# -NEW-AQB-5-ANTON_TRANS-PWR-POLYGON.net
KiCad netlist of a schematic drawn in Altium Designer
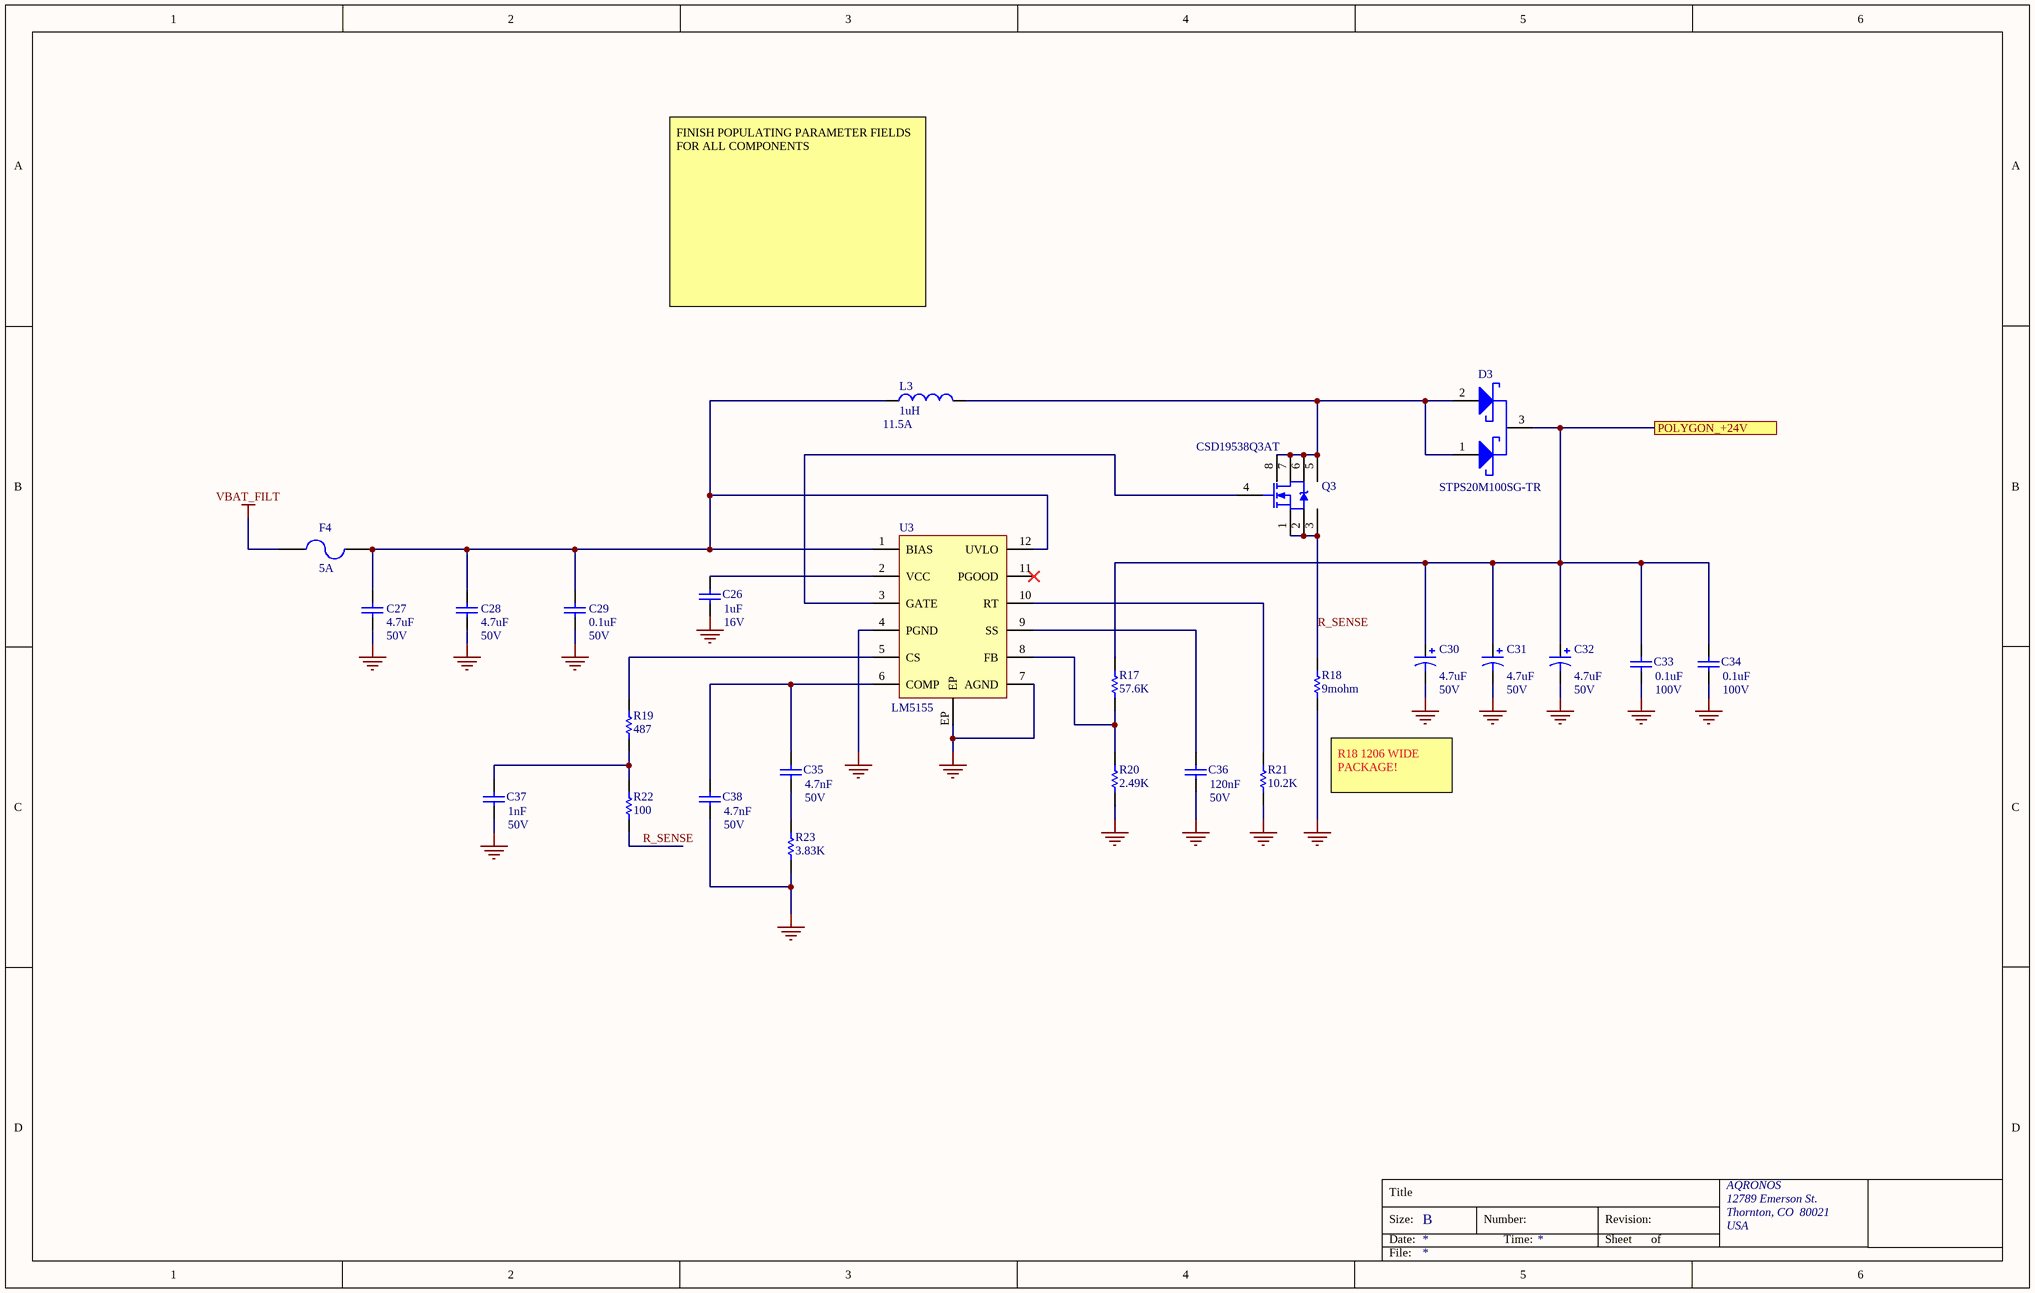
[diagram p0: -NEW-AQB-5-ANTON_TRANS-PWR-POLYGON.SchDoc]

(export (version "E")
  (design (tool "Eeschema 10.0.6"))
  (components
    (comp (ref "C26")
      (value "1uF")
      (footprint "CAP0603")
      (description "CAP CER 1UF 16V X7R 0603")
      (fields
        (field (name "DISTRIBUTOR PART NUMBER") "587-1241-1-ND")
        (field (name "MANUFACTURER PART NUMBER") "EMK107B7105KA-T")
        (field (name "VOLTAGE") "16V")
      )
      (libsource (lib "AQRONOS_TEMP_SCH") (part "Capacitor_non_pol"))
    )
    (comp (ref "C27")
      (value "4.7uF")
      (footprint "CAP0805")
      (description "CAP CER 4.7UF 50V X5R 0805")
      (fields
        (field (name "DISTRIBUTOR PART NUMBER") "445-5980-1-ND")
        (field (name "MANUFACTURER PART NUMBER") "C2012X5R1H475K125AB")
        (field (name "VOLTAGE") "50V")
      )
      (libsource (lib "AQRONOS_TEMP_SCH") (part "Capacitor_non_pol"))
    )
    (comp (ref "C28")
      (value "4.7uF")
      (footprint "CAP0805")
      (description "CAP CER 4.7UF 50V X5R 0805")
      (fields
        (field (name "DISTRIBUTOR PART NUMBER") "445-5980-1-ND")
        (field (name "MANUFACTURER PART NUMBER") "C2012X5R1H475K125AB")
        (field (name "VOLTAGE") "50V")
      )
      (libsource (lib "AQRONOS_TEMP_SCH") (part "Capacitor_non_pol"))
    )
    (comp (ref "C29")
      (value "0.1uF")
      (footprint "CAP0402")
      (description "CAP CER 0.1UF 50V X5R 0402")
      (fields
        (field (name "DISTRIBUTOR PART NUMBER") "445-5942-1-ND")
        (field (name "MANUFACTURER PART NUMBER") "C1005X5R1H104K050BB")
        (field (name "VOLTAGE") "50V")
      )
      (libsource (lib "AQRONOS_TEMP_SCH") (part "Capacitor_non_pol"))
    )
    (comp (ref "C30")
      (value "4.7uF")
      (footprint "CAP1206")
      (description "CAP CER 4.7UF 50V X7R 1206")
      (fields
        (field (name "DISTRIBUTOR PART NUMBER") "490-6521-1-ND")
        (field (name "MANUFACTURER PART NUMBER") "C2012X5R1H475K125AB")
        (field (name "VOLTAGE") "50V")
      )
      (libsource (lib "AQRONOS_TEMP_SCH") (part "Capacitor-Polarized"))
    )
    (comp (ref "C31")
      (value "4.7uF")
      (footprint "CAP1206")
      (description "CAP CER 4.7UF 50V X7R 1206")
      (fields
        (field (name "DISTRIBUTOR PART NUMBER") "490-6521-1-ND")
        (field (name "MANUFACTURER PART NUMBER") "C2012X5R1H475K125AB")
        (field (name "VOLTAGE") "50V")
      )
      (libsource (lib "AQRONOS_TEMP_SCH") (part "Capacitor-Polarized"))
    )
    (comp (ref "C32")
      (value "4.7uF")
      (footprint "CAP1206")
      (description "CAP CER 4.7UF 50V X7R 1206")
      (fields
        (field (name "DISTRIBUTOR PART NUMBER") "490-6521-1-ND")
        (field (name "MANUFACTURER PART NUMBER") "C2012X5R1H475K125AB")
        (field (name "VOLTAGE") "50V")
      )
      (libsource (lib "AQRONOS_TEMP_SCH") (part "Capacitor-Polarized"))
    )
    (comp (ref "C33")
      (value "0.1uF")
      (footprint "CAP0603")
      (description "CAP CER 0.1UF 100V X7R 0603")
      (fields
        (field (name "DISTRIBUTOR PART NUMBER") "490-3285-1-ND")
        (field (name "MANUFACTURER PART NUMBER") "GRM188R72A104KA35D")
        (field (name "VOLTAGE") "100V")
      )
      (libsource (lib "AQRONOS_TEMP_SCH") (part "Capacitor_non_pol"))
    )
    (comp (ref "C34")
      (value "0.1uF")
      (footprint "CAP0603")
      (description "CAP CER 0.1UF 100V X7R 0603")
      (fields
        (field (name "DISTRIBUTOR PART NUMBER") "490-3285-1-ND")
        (field (name "MANUFACTURER PART NUMBER") "GRM188R72A104KA35D")
        (field (name "VOLTAGE") "100V")
      )
      (libsource (lib "AQRONOS_TEMP_SCH") (part "Capacitor_non_pol"))
    )
    (comp (ref "C35")
      (value "4.7nF")
      (footprint "CAP0603")
      (description "CAP CER 4700PF 50V C0G 0603")
      (fields
        (field (name "DISTRIBUTOR PART NUMBER") "445-6912-1-ND")
        (field (name "MANUFACTURER PART NUMBER") "CGA3E2C0G1H472J080AA")
        (field (name "VOLTAGE") "50V")
      )
      (libsource (lib "AQRONOS_TEMP_SCH") (part "Capacitor_non_pol"))
    )
    (comp (ref "C36")
      (value "120nF")
      (footprint "CAP0402")
      (fields
        (field (name "DISTRIBUTOR PART NUMBER") "490-1311-1-ND")
        (field (name "MANUFACTURER PART NUMBER") "C1812C124J5GACTU")
        (field (name "VOLTAGE") "50V")
        (field (name "Comment") "Capacitor_non_pol")
      )
      (libsource (lib "AQRONOS_TEMP_SCH") (part "Capacitor_non_pol"))
    )
    (comp (ref "C37")
      (value "1nF")
      (footprint "CAP0402")
      (description "CAP CER 1000PF 50V C0G/NP0 0402")
      (fields
        (field (name "DISTRIBUTOR PART NUMBER") "490-6190-1-ND")
        (field (name "MANUFACTURER PART NUMBER") "GRM1555C1H102JA01J")
        (field (name "VOLTAGE") "50V")
      )
      (libsource (lib "AQRONOS_TEMP_SCH") (part "Capacitor_non_pol"))
    )
    (comp (ref "C38")
      (value "4.7nF")
      (footprint "CAP0603")
      (description "CAP CER 4700PF 50V C0G 0603")
      (fields
        (field (name "DISTRIBUTOR PART NUMBER") "445-6912-1-ND")
        (field (name "MANUFACTURER PART NUMBER") "CGA3E2C0G1H472J080AA")
        (field (name "VOLTAGE") "50V")
      )
      (libsource (lib "AQRONOS_TEMP_SCH") (part "Capacitor_non_pol"))
    )
    (comp (ref "D3")
      (value "Schottky-3-Terminal")
      (footprint "ONSC-D2PAK-3-418AJ_A_V")
      (description "DIODE SCHOTTKY 100V 20A D2PAK")
      (fields
        (field (name "MANUFACTURER") "On Semiconductor")
        (field (name "PARTNUMBER") "STPS20M100SG-TR")
        (field (name "MANUFACTURER PART NUMBER") "STPS20M100SG-TR")
      )
      (libsource (lib "AQRONOS_TEMP_SCH") (part "Schottky-3-Terminal"))
    )
    (comp (ref "F4")
      (value "Fuse")
      (footprint "RES0603")
      (description "FUSE BOARD MNT 5A 32VAC/VDC 0603")
      (fields
        (field (name "MANUFACTURER PART NUMBER") "TR/0603FA5-R")
        (field (name "MANUFACTURER") "Eaton")
        (field (name "CURRENT") "5A")
        (field (name "PUBLISHER") "Altium Limited")
      )
      (libsource (lib "AQRONOS_TEMP_SCH") (part "Fuse"))
    )
    (comp (ref "L3")
      (value "1uH")
      (footprint "PA4320.104NLT")
      (description "Fixed Inductors 4.7uH 20% 11A 14.40mOhms AEC-Q200")
      (fields
        (field (name "DISTRIBUTOR PART NUMBER") "732-6176-1-ND")
        (field (name "MANUFACTURER PART NUMBER") "744316100")
        (field (name "CURRENT") "11.5A")
      )
      (libsource (lib "AQRONOS_TEMP_SCH") (part "Inductor"))
    )
    (comp (ref "Q3")
      (value "CSD19538Q3AT")
      (footprint "CSD18531Q5A-3D")
      (fields
        (field (name "MANUFACTURER PART NUMBER") "CSD18543Q3A")
        (field (name "DISTRIBUTOR PART NUMBER") "296-45302-1-ND")
        (field (name "PUBLISHER") "Altium Limited")
      )
      (libsource (lib "AQRONOS_TEMP_SCH") (part "CSD18531Q5A"))
    )
    (comp (ref "R17")
      (value "57.6K")
      (footprint "RES0402")
      (fields
        (field (name "DISTRIBUTOR PART NUMBER") "RG16P57.6KBCT-ND")
        (field (name "MANUFACTURER PART NUMBER") "RG1608P-5762-B-T5")
        (field (name "Comment") "Resistor")
      )
      (libsource (lib "AQRONOS_TEMP_SCH") (part "Resistor"))
    )
    (comp (ref "R18")
      (value "9mohm")
      (description "RES 0.009 OHM 1W 1206 WIDE")
      (fields
        (field (name "DISTRIBUTOR PART NUMBER") "PRL1632.009FCT-ND")
        (field (name "MANUFACTURER PART NUMBER") "PRL1632-R009-F-T1")
      )
      (libsource (lib "AQRONOS_TEMP_SCH") (part "Resistor"))
    )
    (comp (ref "R19")
      (value "487")
      (footprint "RES0402")
      (description "RES SMD 487 OHM 1% 1/5W 0402")
      (fields
        (field (name "DISTRIBUTOR PART NUMBER") "541-487YCT-ND")
        (field (name "MANUFACTURER PART NUMBER") "CRCW0402487RFKED")
      )
      (libsource (lib "AQRONOS_TEMP_SCH") (part "Resistor"))
    )
    (comp (ref "R20")
      (value "2.49K")
      (footprint "RES0402")
      (fields
        (field (name "DISTRIBUTOR PART NUMBER") "RG16P2.49KBCT-ND")
        (field (name "MANUFACTURER PART NUMBER") "RG1608P-2491-B-T5")
        (field (name "Comment") "Resistor")
      )
      (libsource (lib "AQRONOS_TEMP_SCH") (part "Resistor"))
    )
    (comp (ref "R21")
      (value "10.2K")
      (footprint "RES0402")
      (description "RES SMD 10.2KOHM 0.1% 1/16W 0402")
      (fields
        (field (name "DISTRIBUTOR PART NUMBER") "P10.2KDCCT-ND")
        (field (name "MANUFACTURER PART NUMBER") "ERA-2AEB1022X")
      )
      (libsource (lib "AQRONOS_TEMP_SCH") (part "Resistor"))
    )
    (comp (ref "R22")
      (value "100")
      (footprint "RES0402")
      (description "RES SMD 100 OHM 1% 1/16W 0402")
      (fields
        (field (name "DISTRIBUTOR PART NUMBER") "541-100LCT-ND")
        (field (name "MANUFACTURER PART NUMBER") "CRCW0402100RFKED")
      )
      (libsource (lib "AQRONOS_TEMP_SCH") (part "Resistor"))
    )
    (comp (ref "R23")
      (value "3.83K")
      (footprint "RES0603")
      (description "RES SMD 3.83KOHM 0.1% 1/10W 0603")
      (fields
        (field (name "DISTRIBUTOR PART NUMBER") "YAG4549CT-ND")
        (field (name "MANUFACTURER PART NUMBER") "RT0603BRD073K83L")
      )
      (libsource (lib "AQRONOS_TEMP_SCH") (part "Resistor"))
    )
    (comp (ref "U3")
      (value "LM5155")
      (footprint "LM155 WSON")
      (description "60V Low Side Controller for Boost and SEPIC, 10-pin MSOP, Pb-Free")
      (fields
        (field (name "MANUFACTURER PART NUMBER") "LM51551DSST")
        (field (name "DISTRIBUTOR PART NUMBER") "296-53427-1-ND")
      )
      (libsource (lib "AQRONOS_TEMP_SCH") (part "LM5155"))
    )
  )
  (nets
    (net (code "1") (name "/POLYGON_+24V") (class "Default")
      (node (ref "C30") (pin "1") (pinfunction "1_1") (pintype "passive"))
      (node (ref "C31") (pin "1") (pinfunction "1_1") (pintype "passive"))
      (node (ref "C32") (pin "1") (pinfunction "1_1") (pintype "passive"))
      (node (ref "C33") (pin "1") (pinfunction "1_1") (pintype "passive"))
      (node (ref "C34") (pin "1") (pinfunction "1_1") (pintype "passive"))
      (node (ref "D3") (pin "3") (pinfunction "K_3") (pintype "passive"))
      (node (ref "R17") (pin "1") (pinfunction "1_1") (pintype "passive"))
    )
    (net (code "2") (name "/R_SENSE") (class "Default")
      (node (ref "Q3") (pin "1") (pinfunction "S_1") (pintype "passive"))
      (node (ref "Q3") (pin "2") (pinfunction "S_2") (pintype "passive"))
      (node (ref "Q3") (pin "3") (pinfunction "S_3") (pintype "passive"))
      (node (ref "R18") (pin "2") (pinfunction "2_2") (pintype "passive"))
      (node (ref "R22") (pin "2") (pinfunction "2_2") (pintype "passive"))
    )
    (net (code "3") (name "GND") (class "Default")
      (node (ref "C26") (pin "2") (pinfunction "2_2") (pintype "passive"))
      (node (ref "C27") (pin "2") (pinfunction "2_2") (pintype "passive"))
      (node (ref "C28") (pin "2") (pinfunction "2_2") (pintype "passive"))
      (node (ref "C29") (pin "2") (pinfunction "2_2") (pintype "passive"))
      (node (ref "C30") (pin "2") (pinfunction "2_2") (pintype "passive"))
      (node (ref "C31") (pin "2") (pinfunction "2_2") (pintype "passive"))
      (node (ref "C32") (pin "2") (pinfunction "2_2") (pintype "passive"))
      (node (ref "C33") (pin "2") (pinfunction "2_2") (pintype "passive"))
      (node (ref "C34") (pin "2") (pinfunction "2_2") (pintype "passive"))
      (node (ref "C36") (pin "2") (pinfunction "2_2") (pintype "passive"))
      (node (ref "C37") (pin "2") (pinfunction "2_2") (pintype "passive"))
      (node (ref "C38") (pin "2") (pinfunction "2_2") (pintype "passive"))
      (node (ref "R18") (pin "1") (pinfunction "1_1") (pintype "passive"))
      (node (ref "R20") (pin "2") (pinfunction "2_2") (pintype "passive"))
      (node (ref "R21") (pin "2") (pinfunction "2_2") (pintype "passive"))
      (node (ref "R23") (pin "2") (pinfunction "2_2") (pintype "passive"))
      (node (ref "U3") (pin "4") (pinfunction "PGND_4") (pintype "power_in"))
      (node (ref "U3") (pin "7") (pinfunction "AGND_7") (pintype "passive"))
      (node (ref "U3") (pin "EP") (pinfunction "EP_EP") (pintype "power_in"))
    )
    (net (code "4") (name "Net-(C35-Pad2)") (class "Default")
      (node (ref "C35") (pin "2") (pinfunction "2_2") (pintype "passive"))
      (node (ref "R23") (pin "1") (pinfunction "1_1") (pintype "passive"))
    )
    (net (code "5") (name "Net-(C37-Pad1)") (class "Default")
      (node (ref "C37") (pin "1") (pinfunction "1_1") (pintype "passive"))
      (node (ref "R19") (pin "1") (pinfunction "1_1") (pintype "passive"))
      (node (ref "R22") (pin "1") (pinfunction "1_1") (pintype "passive"))
    )
    (net (code "6") (name "Net-(D3-A-Pad1)") (class "Default")
      (node (ref "D3") (pin "1") (pinfunction "A_1") (pintype "passive"))
      (node (ref "D3") (pin "2") (pinfunction "A_2") (pintype "passive"))
      (node (ref "L3") (pin "2") (pinfunction "2_2") (pintype "passive"))
      (node (ref "Q3") (pin "5") (pinfunction "D_5") (pintype "passive"))
      (node (ref "Q3") (pin "6") (pinfunction "D_6") (pintype "passive"))
      (node (ref "Q3") (pin "7") (pinfunction "D_7") (pintype "passive"))
      (node (ref "Q3") (pin "8") (pinfunction "D_8") (pintype "passive"))
    )
    (net (code "7") (name "Net-(Q3-G)") (class "Default")
      (node (ref "Q3") (pin "4") (pinfunction "G_4") (pintype "passive"))
      (node (ref "U3") (pin "3") (pinfunction "GATE_3") (pintype "power_in"))
    )
    (net (code "8") (name "Net-(U3-BIAS)") (class "Default")
      (node (ref "C27") (pin "1") (pinfunction "1_1") (pintype "passive"))
      (node (ref "C28") (pin "1") (pinfunction "1_1") (pintype "passive"))
      (node (ref "C29") (pin "1") (pinfunction "1_1") (pintype "passive"))
      (node (ref "F4") (pin "2") (pinfunction "2_2") (pintype "passive"))
      (node (ref "L3") (pin "1") (pinfunction "1_1") (pintype "passive"))
      (node (ref "U3") (pin "1") (pinfunction "BIAS_1") (pintype "power_in"))
      (node (ref "U3") (pin "12") (pinfunction "UVLO_12") (pintype "power_in"))
    )
    (net (code "9") (name "Net-(U3-COMP)") (class "Default")
      (node (ref "C35") (pin "1") (pinfunction "1_1") (pintype "passive"))
      (node (ref "C38") (pin "1") (pinfunction "1_1") (pintype "passive"))
      (node (ref "U3") (pin "6") (pinfunction "COMP_6") (pintype "power_in"))
    )
    (net (code "10") (name "Net-(U3-CS)") (class "Default")
      (node (ref "R19") (pin "2") (pinfunction "2_2") (pintype "passive"))
      (node (ref "U3") (pin "5") (pinfunction "CS_5") (pintype "power_in"))
    )
    (net (code "11") (name "Net-(U3-FB)") (class "Default")
      (node (ref "R17") (pin "2") (pinfunction "2_2") (pintype "passive"))
      (node (ref "R20") (pin "1") (pinfunction "1_1") (pintype "passive"))
      (node (ref "U3") (pin "8") (pinfunction "FB_8") (pintype "power_in"))
    )
    (net (code "12") (name "Net-(U3-RT)") (class "Default")
      (node (ref "R21") (pin "1") (pinfunction "1_1") (pintype "passive"))
      (node (ref "U3") (pin "10") (pinfunction "RT_10") (pintype "power_in"))
    )
    (net (code "13") (name "Net-(U3-SS)") (class "Default")
      (node (ref "C36") (pin "1") (pinfunction "1_1") (pintype "passive"))
      (node (ref "U3") (pin "9") (pinfunction "SS_9") (pintype "power_in"))
    )
    (net (code "14") (name "Net-(U3-VCC)") (class "Default")
      (node (ref "C26") (pin "1") (pinfunction "1_1") (pintype "passive"))
      (node (ref "U3") (pin "2") (pinfunction "VCC_2") (pintype "power_in"))
    )
    (net (code "15") (name "VBAT_FILT") (class "Default")
      (node (ref "F4") (pin "1") (pinfunction "1_1") (pintype "passive"))
    )
    (net (code "16") (name "unconnected-(U3-PGOOD-Pad11)") (class "Default")
      (node (ref "U3") (pin "11") (pinfunction "PGOOD_11") (pintype "power_in+no_connect"))
    )
  )
)
